# Sensor_atras.net
KiCad netlist of a schematic drawn in EAGLE
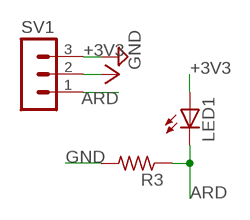
[diagram p0: schematic, sheet 1]

(export (version "E")
  (design (tool "Eeschema 10.0.6"))
  (components
    (comp (ref "LED1")
      (value "LED5MM")
      (footprint "eagle-import:LED5MM")
      (libsource (lib "eagle-import") (part "LED5MM"))
    )
    (comp (ref "R3")
      (value "R-US_0207/15")
      (footprint "eagle-import:0207_15")
      (libsource (lib "eagle-import") (part "R-US_0207/15"))
    )
    (comp (ref "SV1")
      (value "MA03-1")
      (footprint "eagle-import:MA03-1")
      (libsource (lib "eagle-import") (part "MA03-1"))
    )
  )
  (nets
    (net (code "1") (name "+3V3") (class "Default")
      (node (ref "LED1") (pin "A") (pinfunction "A_A") (pintype "passive"))
      (node (ref "SV1") (pin "2") (pinfunction "2_2") (pintype "passive"))
    )
    (net (code "2") (name "/ARD") (class "Default")
      (node (ref "LED1") (pin "K") (pinfunction "C_K") (pintype "passive"))
      (node (ref "R3") (pin "1") (pinfunction "1_1") (pintype "passive"))
      (node (ref "SV1") (pin "1") (pinfunction "1_1") (pintype "passive"))
    )
    (net (code "3") (name "GND") (class "Default")
      (node (ref "R3") (pin "2") (pinfunction "2_2") (pintype "passive"))
      (node (ref "SV1") (pin "3") (pinfunction "3_3") (pintype "passive"))
    )
  )
)
